# CCM_0008.net
KiCad netlist of a schematic drawn in EAGLE
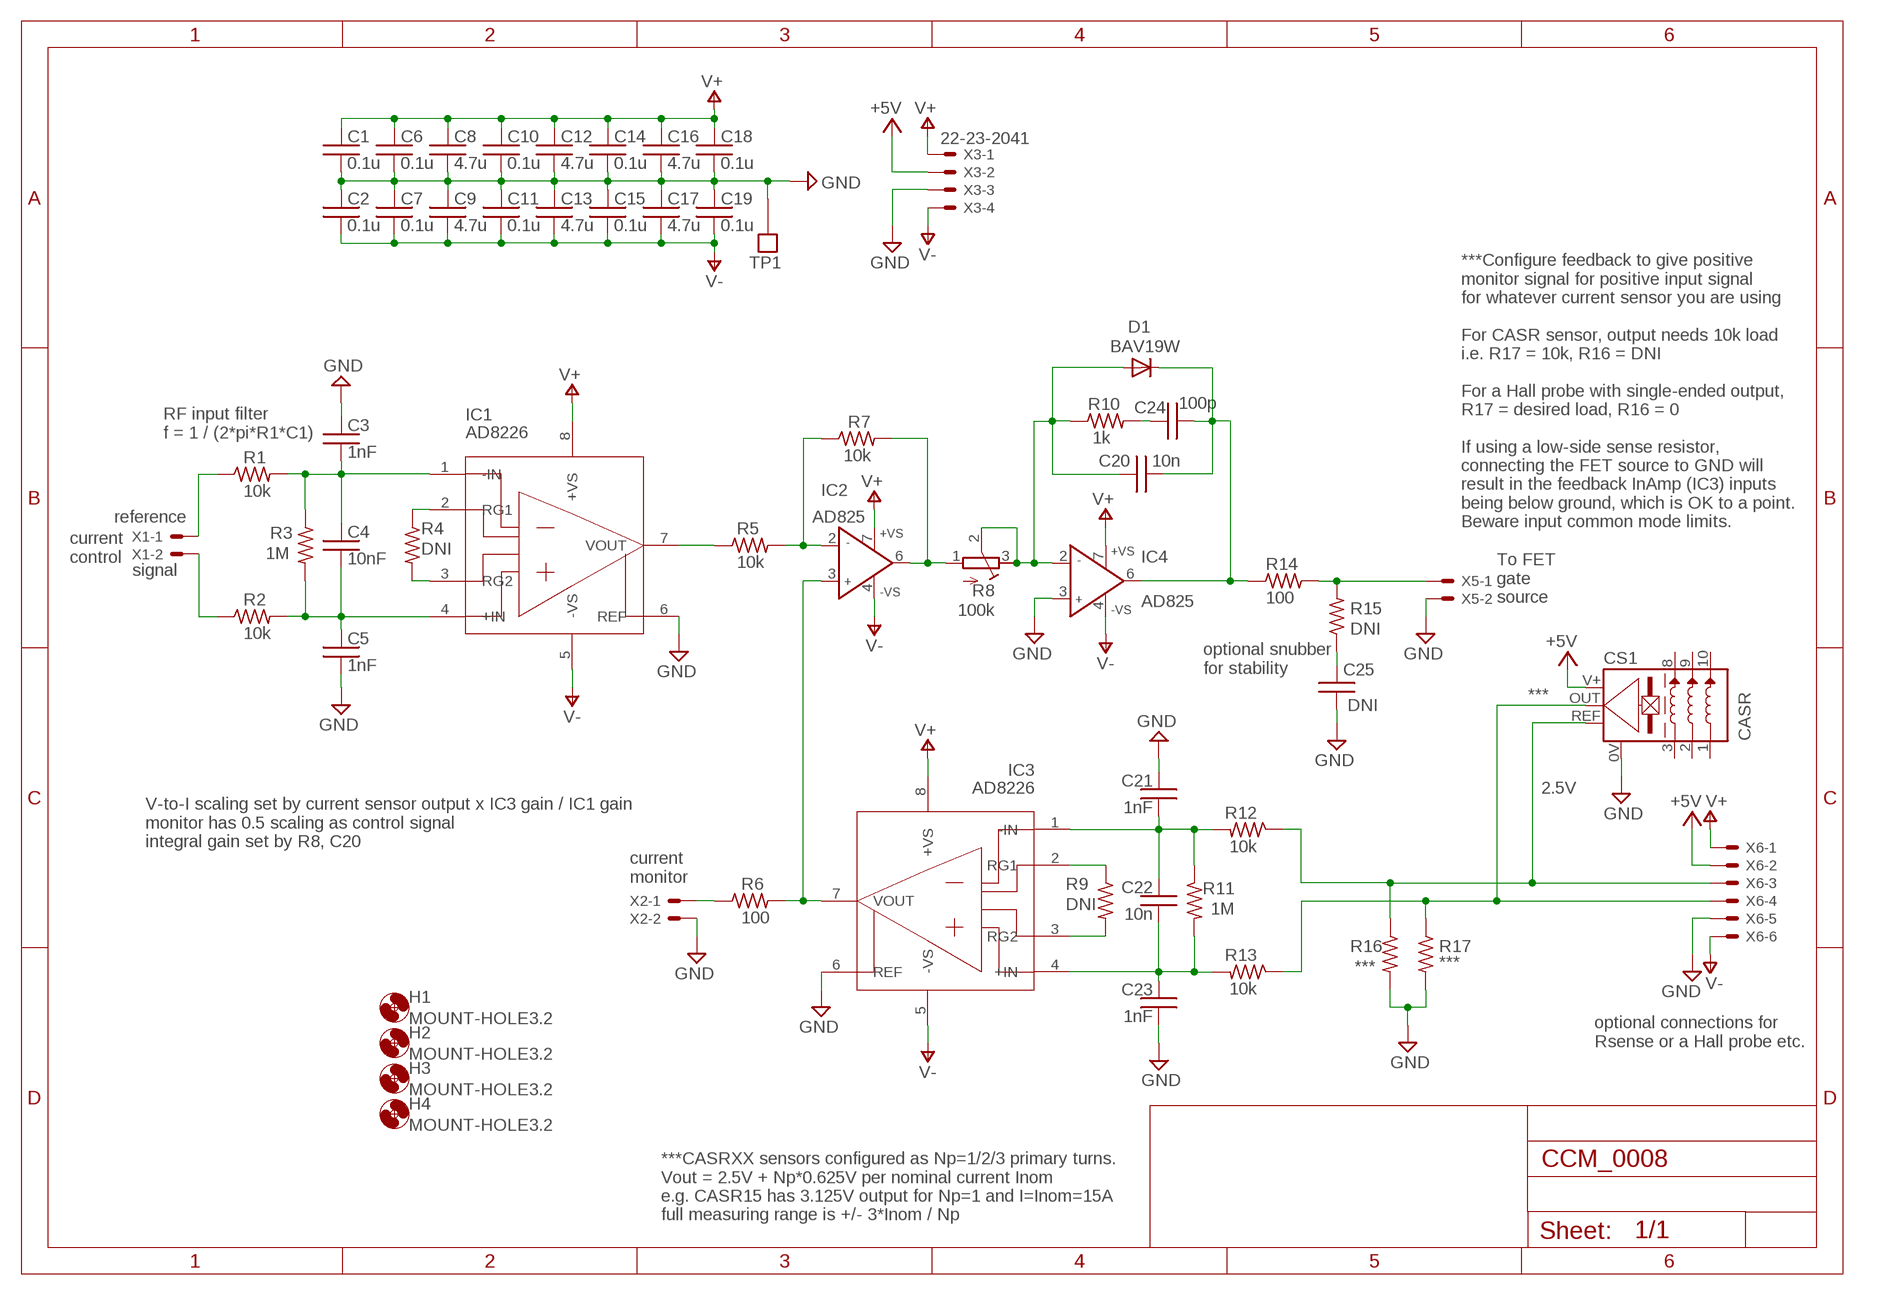
[diagram p0: schematic, sheet 1]

(export (version "E")
  (design (tool "Eeschema 10.0.6"))
  (components
    (comp (ref "C1")
      (value "0.1u")
      (footprint "eagle-import:0603")
      (libsource (lib "eagle-import") (part "C0603"))
    )
    (comp (ref "C2")
      (value "0.1u")
      (footprint "eagle-import:0603")
      (libsource (lib "eagle-import") (part "C0603"))
    )
    (comp (ref "C3")
      (value "1nF")
      (footprint "eagle-import:0603")
      (libsource (lib "eagle-import") (part "C0603"))
    )
    (comp (ref "C4")
      (value "10nF")
      (footprint "eagle-import:0603")
      (libsource (lib "eagle-import") (part "C0603"))
    )
    (comp (ref "C5")
      (value "1nF")
      (footprint "eagle-import:0603")
      (libsource (lib "eagle-import") (part "C0603"))
    )
    (comp (ref "C6")
      (value "0.1u")
      (footprint "eagle-import:0603")
      (libsource (lib "eagle-import") (part "C0603"))
    )
    (comp (ref "C7")
      (value "0.1u")
      (footprint "eagle-import:0603")
      (libsource (lib "eagle-import") (part "C0603"))
    )
    (comp (ref "C8")
      (value "4.7u")
      (footprint "eagle-import:0603")
      (libsource (lib "eagle-import") (part "C0603"))
    )
    (comp (ref "C9")
      (value "4.7u")
      (footprint "eagle-import:0603")
      (libsource (lib "eagle-import") (part "C0603"))
    )
    (comp (ref "C10")
      (value "0.1u")
      (footprint "eagle-import:0603")
      (libsource (lib "eagle-import") (part "C0603"))
    )
    (comp (ref "C11")
      (value "0.1u")
      (footprint "eagle-import:0603")
      (libsource (lib "eagle-import") (part "C0603"))
    )
    (comp (ref "C12")
      (value "4.7u")
      (footprint "eagle-import:0603")
      (libsource (lib "eagle-import") (part "C0603"))
    )
    (comp (ref "C13")
      (value "4.7u")
      (footprint "eagle-import:0603")
      (libsource (lib "eagle-import") (part "C0603"))
    )
    (comp (ref "C14")
      (value "0.1u")
      (footprint "eagle-import:0603")
      (libsource (lib "eagle-import") (part "C0603"))
    )
    (comp (ref "C15")
      (value "0.1u")
      (footprint "eagle-import:0603")
      (libsource (lib "eagle-import") (part "C0603"))
    )
    (comp (ref "C16")
      (value "4.7u")
      (footprint "eagle-import:0603")
      (libsource (lib "eagle-import") (part "C0603"))
    )
    (comp (ref "C17")
      (value "4.7u")
      (footprint "eagle-import:0603")
      (libsource (lib "eagle-import") (part "C0603"))
    )
    (comp (ref "C18")
      (value "0.1u")
      (footprint "eagle-import:0603")
      (libsource (lib "eagle-import") (part "C0603"))
    )
    (comp (ref "C19")
      (value "0.1u")
      (footprint "eagle-import:0603")
      (libsource (lib "eagle-import") (part "C0603"))
    )
    (comp (ref "C20")
      (value "10n")
      (footprint "eagle-import:0603")
      (libsource (lib "eagle-import") (part "C0603"))
    )
    (comp (ref "C21")
      (value "1nF")
      (footprint "eagle-import:0603")
      (libsource (lib "eagle-import") (part "C0603"))
    )
    (comp (ref "C22")
      (value "10n")
      (footprint "eagle-import:0603")
      (libsource (lib "eagle-import") (part "C0603"))
    )
    (comp (ref "C23")
      (value "1nF")
      (footprint "eagle-import:0603")
      (libsource (lib "eagle-import") (part "C0603"))
    )
    (comp (ref "C24")
      (value "100p")
      (footprint "eagle-import:0603")
      (libsource (lib "eagle-import") (part "C0603"))
    )
    (comp (ref "C25")
      (value "DNI")
      (footprint "eagle-import:0603")
      (libsource (lib "eagle-import") (part "C0603"))
    )
    (comp (ref "CS1")
      (value "CASR")
      (footprint "eagle-import:CASR")
      (libsource (lib "eagle-import") (part "CASR"))
    )
    (comp (ref "D1")
      (value "BAV19W")
      (footprint "eagle-import:SOD123")
      (libsource (lib "eagle-import") (part "DIODE-SOD123"))
    )
    (comp (ref "H1")
      (value "MOUNT-HOLE3.2")
      (footprint "eagle-import:3,2")
      (libsource (lib "eagle-import") (part "MOUNT-HOLE3.2"))
    )
    (comp (ref "H2")
      (value "MOUNT-HOLE3.2")
      (footprint "eagle-import:3,2")
      (libsource (lib "eagle-import") (part "MOUNT-HOLE3.2"))
    )
    (comp (ref "H3")
      (value "MOUNT-HOLE3.2")
      (footprint "eagle-import:3,2")
      (libsource (lib "eagle-import") (part "MOUNT-HOLE3.2"))
    )
    (comp (ref "H4")
      (value "MOUNT-HOLE3.2")
      (footprint "eagle-import:3,2")
      (libsource (lib "eagle-import") (part "MOUNT-HOLE3.2"))
    )
    (comp (ref "IC1")
      (value "AD8226")
      (footprint "eagle-import:SO08")
      (libsource (lib "eagle-import") (part "AD8226"))
    )
    (comp (ref "IC2")
      (value "AD825")
      (footprint "eagle-import:SO8")
      (fields (field (name "MF") "ALTERA CORPORATION") (field (name "MPN") "AD825ARZ"))
      (libsource (lib "eagle-import") (part "AD825_BR"))
    )
    (comp (ref "IC3")
      (value "AD8226")
      (footprint "eagle-import:SO08")
      (libsource (lib "eagle-import") (part "AD8226"))
    )
    (comp (ref "IC4")
      (value "AD825")
      (footprint "eagle-import:SO8")
      (fields (field (name "MF") "ALTERA CORPORATION") (field (name "MPN") "AD825ARZ"))
      (libsource (lib "eagle-import") (part "AD825_BR"))
    )
    (comp (ref "R1")
      (value "10k")
      (footprint "eagle-import:0603")
      (libsource (lib "eagle-import") (part "R0603"))
    )
    (comp (ref "R2")
      (value "10k")
      (footprint "eagle-import:0603")
      (libsource (lib "eagle-import") (part "R0603"))
    )
    (comp (ref "R3")
      (value "1M")
      (footprint "eagle-import:0603")
      (libsource (lib "eagle-import") (part "R0603"))
    )
    (comp (ref "R4")
      (value "DNI")
      (footprint "eagle-import:0603")
      (libsource (lib "eagle-import") (part "R0603"))
    )
    (comp (ref "R5")
      (value "10k")
      (footprint "eagle-import:0603")
      (libsource (lib "eagle-import") (part "R0603"))
    )
    (comp (ref "R6")
      (value "100")
      (footprint "eagle-import:0603")
      (libsource (lib "eagle-import") (part "R0603"))
    )
    (comp (ref "R7")
      (value "10k")
      (footprint "eagle-import:0603")
      (libsource (lib "eagle-import") (part "R0603"))
    )
    (comp (ref "R8")
      (value "100k")
      (footprint "eagle-import:RTRIM3296W")
      (libsource (lib "eagle-import") (part "R-TRIMM3296W"))
    )
    (comp (ref "R9")
      (value "DNI")
      (footprint "eagle-import:0603")
      (libsource (lib "eagle-import") (part "R0603"))
    )
    (comp (ref "R10")
      (value "1k")
      (footprint "eagle-import:0603")
      (libsource (lib "eagle-import") (part "R0603"))
    )
    (comp (ref "R11")
      (value "1M")
      (footprint "eagle-import:0603")
      (libsource (lib "eagle-import") (part "R0603"))
    )
    (comp (ref "R12")
      (value "10k")
      (footprint "eagle-import:0603")
      (libsource (lib "eagle-import") (part "R0603"))
    )
    (comp (ref "R13")
      (value "10k")
      (footprint "eagle-import:0603")
      (libsource (lib "eagle-import") (part "R0603"))
    )
    (comp (ref "R14")
      (value "100")
      (footprint "eagle-import:0603")
      (libsource (lib "eagle-import") (part "R0603"))
    )
    (comp (ref "R15")
      (value "DNI")
      (footprint "eagle-import:0603")
      (libsource (lib "eagle-import") (part "R0603"))
    )
    (comp (ref "R16")
      (value "***")
      (footprint "eagle-import:0603")
      (libsource (lib "eagle-import") (part "R0603"))
    )
    (comp (ref "R17")
      (value "***")
      (footprint "eagle-import:0603")
      (libsource (lib "eagle-import") (part "R0603"))
    )
    (comp (ref "TP1")
      (value "TESTPOINT")
      (footprint "eagle-import:TESTPOINT")
      (libsource (lib "eagle-import") (part "TESTPOINT"))
    )
    (comp (ref "X1")
      (value "22-23-2021")
      (footprint "eagle-import:22-23-2021")
      (fields (field (name "MF") "MOLEX"))
      (libsource (lib "eagle-import") (part "22-23-2021"))
    )
    (comp (ref "X2")
      (value "22-23-2021")
      (footprint "eagle-import:22-23-2021")
      (fields (field (name "MF") "MOLEX"))
      (libsource (lib "eagle-import") (part "22-23-2021"))
    )
    (comp (ref "X3")
      (value "22-23-2041")
      (footprint "eagle-import:22-23-2041")
      (fields (field (name "MF") "MOLEX"))
      (libsource (lib "eagle-import") (part "22-23-2041"))
    )
    (comp (ref "X5")
      (value "22-23-2021")
      (footprint "eagle-import:22-23-2021")
      (fields (field (name "MF") "MOLEX"))
      (libsource (lib "eagle-import") (part "22-23-2021"))
    )
    (comp (ref "X6")
      (value "22-23-2061")
      (footprint "eagle-import:22-23-2061")
      (fields (field (name "MF") "MOLEX"))
      (libsource (lib "eagle-import") (part "22-23-2061"))
    )
  )
  (nets
    (net (code "1") (name "+5V") (class "Default")
      (node (ref "CS1") (pin "V+") (pinfunction "V+_V+") (pintype "input"))
      (node (ref "X3") (pin "2") (pinfunction "S_2") (pintype "passive"))
      (node (ref "X6") (pin "2") (pinfunction "S_2") (pintype "passive"))
    )
    (net (code "2") (name "GND") (class "Default")
      (node (ref "C1") (pin "2") (pinfunction "2_2") (pintype "passive"))
      (node (ref "C10") (pin "2") (pinfunction "2_2") (pintype "passive"))
      (node (ref "C11") (pin "1") (pinfunction "1_1") (pintype "passive"))
      (node (ref "C12") (pin "2") (pinfunction "2_2") (pintype "passive"))
      (node (ref "C13") (pin "1") (pinfunction "1_1") (pintype "passive"))
      (node (ref "C14") (pin "2") (pinfunction "2_2") (pintype "passive"))
      (node (ref "C15") (pin "1") (pinfunction "1_1") (pintype "passive"))
      (node (ref "C16") (pin "2") (pinfunction "2_2") (pintype "passive"))
      (node (ref "C17") (pin "1") (pinfunction "1_1") (pintype "passive"))
      (node (ref "C18") (pin "2") (pinfunction "2_2") (pintype "passive"))
      (node (ref "C19") (pin "1") (pinfunction "1_1") (pintype "passive"))
      (node (ref "C2") (pin "1") (pinfunction "1_1") (pintype "passive"))
      (node (ref "C21") (pin "1") (pinfunction "1_1") (pintype "passive"))
      (node (ref "C23") (pin "2") (pinfunction "2_2") (pintype "passive"))
      (node (ref "C25") (pin "2") (pinfunction "2_2") (pintype "passive"))
      (node (ref "C3") (pin "1") (pinfunction "1_1") (pintype "passive"))
      (node (ref "C5") (pin "2") (pinfunction "2_2") (pintype "passive"))
      (node (ref "C6") (pin "2") (pinfunction "2_2") (pintype "passive"))
      (node (ref "C7") (pin "1") (pinfunction "1_1") (pintype "passive"))
      (node (ref "C8") (pin "2") (pinfunction "2_2") (pintype "passive"))
      (node (ref "C9") (pin "1") (pinfunction "1_1") (pintype "passive"))
      (node (ref "CS1") (pin "0V") (pinfunction "0V_0V") (pintype "input"))
      (node (ref "IC1") (pin "6") (pinfunction "REF_6") (pintype "bidirectional"))
      (node (ref "IC3") (pin "6") (pinfunction "REF_6") (pintype "bidirectional"))
      (node (ref "IC4") (pin "3") (pinfunction "IN+_3") (pintype "input"))
      (node (ref "R16") (pin "2") (pinfunction "2_2") (pintype "passive"))
      (node (ref "R17") (pin "2") (pinfunction "2_2") (pintype "passive"))
      (node (ref "TP1") (pin "P$1") (pinfunction "P$1_P$1") (pintype "bidirectional"))
      (node (ref "X2") (pin "2") (pinfunction "S_2") (pintype "passive"))
      (node (ref "X3") (pin "3") (pinfunction "S_3") (pintype "passive"))
      (node (ref "X5") (pin "2") (pinfunction "S_2") (pintype "passive"))
      (node (ref "X6") (pin "5") (pinfunction "S_5") (pintype "passive"))
    )
    (net (code "3") (name "Net-(C24-Pad2)") (class "Default")
      (node (ref "C24") (pin "2") (pinfunction "2_2") (pintype "passive"))
      (node (ref "R10") (pin "2") (pinfunction "2_2") (pintype "passive"))
    )
    (net (code "4") (name "Net-(C25-Pad1)") (class "Default")
      (node (ref "C25") (pin "1") (pinfunction "1_1") (pintype "passive"))
      (node (ref "R15") (pin "1") (pinfunction "1_1") (pintype "passive"))
    )
    (net (code "5") (name "Net-(CS1-VOUT)") (class "Default")
      (node (ref "CS1") (pin "OUT") (pinfunction "VOUT_OUT") (pintype "output"))
      (node (ref "R13") (pin "1") (pinfunction "1_1") (pintype "passive"))
      (node (ref "R17") (pin "1") (pinfunction "1_1") (pintype "passive"))
      (node (ref "X6") (pin "4") (pinfunction "S_4") (pintype "passive"))
    )
    (net (code "6") (name "Net-(CS1-VREF)") (class "Default")
      (node (ref "CS1") (pin "REF") (pinfunction "VREF_REF") (pintype "output"))
      (node (ref "R12") (pin "1") (pinfunction "1_1") (pintype "passive"))
      (node (ref "R16") (pin "1") (pinfunction "1_1") (pintype "passive"))
      (node (ref "X6") (pin "3") (pinfunction "S_3") (pintype "passive"))
    )
    (net (code "7") (name "Net-(IC1-+IN)") (class "Default")
      (node (ref "C4") (pin "2") (pinfunction "2_2") (pintype "passive"))
      (node (ref "C5") (pin "1") (pinfunction "1_1") (pintype "passive"))
      (node (ref "IC1") (pin "4") (pinfunction "+IN_4") (pintype "bidirectional"))
      (node (ref "R2") (pin "2") (pinfunction "2_2") (pintype "passive"))
      (node (ref "R3") (pin "2") (pinfunction "2_2") (pintype "passive"))
    )
    (net (code "8") (name "Net-(IC1--IN)") (class "Default")
      (node (ref "C3") (pin "2") (pinfunction "2_2") (pintype "passive"))
      (node (ref "C4") (pin "1") (pinfunction "1_1") (pintype "passive"))
      (node (ref "IC1") (pin "1") (pinfunction "-IN_1") (pintype "bidirectional"))
      (node (ref "R1") (pin "2") (pinfunction "2_2") (pintype "passive"))
      (node (ref "R3") (pin "1") (pinfunction "1_1") (pintype "passive"))
    )
    (net (code "9") (name "Net-(IC1-RG1)") (class "Default")
      (node (ref "IC1") (pin "2") (pinfunction "RG1_2") (pintype "bidirectional"))
      (node (ref "R4") (pin "1") (pinfunction "1_1") (pintype "passive"))
    )
    (net (code "10") (name "Net-(IC1-RG2)") (class "Default")
      (node (ref "IC1") (pin "3") (pinfunction "RG2_3") (pintype "bidirectional"))
      (node (ref "R4") (pin "2") (pinfunction "2_2") (pintype "passive"))
    )
    (net (code "11") (name "Net-(IC1-VOUT)") (class "Default")
      (node (ref "IC1") (pin "7") (pinfunction "VOUT_7") (pintype "bidirectional"))
      (node (ref "R5") (pin "1") (pinfunction "1_1") (pintype "passive"))
    )
    (net (code "12") (name "Net-(IC2-IN+)") (class "Default")
      (node (ref "IC2") (pin "3") (pinfunction "IN+_3") (pintype "input"))
      (node (ref "IC3") (pin "7") (pinfunction "VOUT_7") (pintype "bidirectional"))
      (node (ref "R6") (pin "2") (pinfunction "2_2") (pintype "passive"))
    )
    (net (code "13") (name "Net-(IC2-IN-)") (class "Default")
      (node (ref "IC2") (pin "2") (pinfunction "IN-_2") (pintype "input"))
      (node (ref "R5") (pin "2") (pinfunction "2_2") (pintype "passive"))
      (node (ref "R7") (pin "1") (pinfunction "1_1") (pintype "passive"))
    )
    (net (code "14") (name "Net-(IC2-OUT)") (class "Default")
      (node (ref "IC2") (pin "6") (pinfunction "OUT_6") (pintype "output"))
      (node (ref "R7") (pin "2") (pinfunction "2_2") (pintype "passive"))
      (node (ref "R8") (pin "1") (pinfunction "A_1") (pintype "passive"))
    )
    (net (code "15") (name "Net-(IC3-+IN)") (class "Default")
      (node (ref "C22") (pin "2") (pinfunction "2_2") (pintype "passive"))
      (node (ref "C23") (pin "1") (pinfunction "1_1") (pintype "passive"))
      (node (ref "IC3") (pin "4") (pinfunction "+IN_4") (pintype "bidirectional"))
      (node (ref "R11") (pin "2") (pinfunction "2_2") (pintype "passive"))
      (node (ref "R13") (pin "2") (pinfunction "2_2") (pintype "passive"))
    )
    (net (code "16") (name "Net-(IC3--IN)") (class "Default")
      (node (ref "C21") (pin "2") (pinfunction "2_2") (pintype "passive"))
      (node (ref "C22") (pin "1") (pinfunction "1_1") (pintype "passive"))
      (node (ref "IC3") (pin "1") (pinfunction "-IN_1") (pintype "bidirectional"))
      (node (ref "R11") (pin "1") (pinfunction "1_1") (pintype "passive"))
      (node (ref "R12") (pin "2") (pinfunction "2_2") (pintype "passive"))
    )
    (net (code "17") (name "Net-(IC3-RG1)") (class "Default")
      (node (ref "IC3") (pin "2") (pinfunction "RG1_2") (pintype "bidirectional"))
      (node (ref "R9") (pin "1") (pinfunction "1_1") (pintype "passive"))
    )
    (net (code "18") (name "Net-(IC3-RG2)") (class "Default")
      (node (ref "IC3") (pin "3") (pinfunction "RG2_3") (pintype "bidirectional"))
      (node (ref "R9") (pin "2") (pinfunction "2_2") (pintype "passive"))
    )
    (net (code "19") (name "Net-(IC4-IN-)") (class "Default")
      (node (ref "C20") (pin "2") (pinfunction "2_2") (pintype "passive"))
      (node (ref "D1") (pin "A") (pinfunction "A_A") (pintype "passive"))
      (node (ref "IC4") (pin "2") (pinfunction "IN-_2") (pintype "input"))
      (node (ref "R10") (pin "1") (pinfunction "1_1") (pintype "passive"))
      (node (ref "R8") (pin "2") (pinfunction "S_2") (pintype "passive"))
      (node (ref "R8") (pin "3") (pinfunction "E_3") (pintype "passive"))
    )
    (net (code "20") (name "Net-(IC4-OUT)") (class "Default")
      (node (ref "C20") (pin "1") (pinfunction "1_1") (pintype "passive"))
      (node (ref "C24") (pin "1") (pinfunction "1_1") (pintype "passive"))
      (node (ref "D1") (pin "C") (pinfunction "C_C") (pintype "passive"))
      (node (ref "IC4") (pin "6") (pinfunction "OUT_6") (pintype "output"))
      (node (ref "R14") (pin "1") (pinfunction "1_1") (pintype "passive"))
    )
    (net (code "21") (name "Net-(X1A-S)") (class "Default")
      (node (ref "R1") (pin "1") (pinfunction "1_1") (pintype "passive"))
      (node (ref "X1") (pin "1") (pinfunction "S_1") (pintype "passive"))
    )
    (net (code "22") (name "Net-(X1B-S)") (class "Default")
      (node (ref "R2") (pin "1") (pinfunction "1_1") (pintype "passive"))
      (node (ref "X1") (pin "2") (pinfunction "S_2") (pintype "passive"))
    )
    (net (code "23") (name "Net-(X2A-S)") (class "Default")
      (node (ref "R6") (pin "1") (pinfunction "1_1") (pintype "passive"))
      (node (ref "X2") (pin "1") (pinfunction "S_1") (pintype "passive"))
    )
    (net (code "24") (name "Net-(X5A-S)") (class "Default")
      (node (ref "R14") (pin "2") (pinfunction "2_2") (pintype "passive"))
      (node (ref "R15") (pin "2") (pinfunction "2_2") (pintype "passive"))
      (node (ref "X5") (pin "1") (pinfunction "S_1") (pintype "passive"))
    )
    (net (code "25") (name "V+") (class "Default")
      (node (ref "C1") (pin "1") (pinfunction "1_1") (pintype "passive"))
      (node (ref "C10") (pin "1") (pinfunction "1_1") (pintype "passive"))
      (node (ref "C12") (pin "1") (pinfunction "1_1") (pintype "passive"))
      (node (ref "C14") (pin "1") (pinfunction "1_1") (pintype "passive"))
      (node (ref "C16") (pin "1") (pinfunction "1_1") (pintype "passive"))
      (node (ref "C18") (pin "1") (pinfunction "1_1") (pintype "passive"))
      (node (ref "C6") (pin "1") (pinfunction "1_1") (pintype "passive"))
      (node (ref "C8") (pin "1") (pinfunction "1_1") (pintype "passive"))
      (node (ref "IC1") (pin "8") (pinfunction "+VS_8") (pintype "bidirectional"))
      (node (ref "IC2") (pin "7") (pinfunction "+VS_7") (pintype "input"))
      (node (ref "IC3") (pin "8") (pinfunction "+VS_8") (pintype "bidirectional"))
      (node (ref "IC4") (pin "7") (pinfunction "+VS_7") (pintype "input"))
      (node (ref "X3") (pin "1") (pinfunction "S_1") (pintype "passive"))
      (node (ref "X6") (pin "1") (pinfunction "S_1") (pintype "passive"))
    )
    (net (code "26") (name "V-") (class "Default")
      (node (ref "C11") (pin "2") (pinfunction "2_2") (pintype "passive"))
      (node (ref "C13") (pin "2") (pinfunction "2_2") (pintype "passive"))
      (node (ref "C15") (pin "2") (pinfunction "2_2") (pintype "passive"))
      (node (ref "C17") (pin "2") (pinfunction "2_2") (pintype "passive"))
      (node (ref "C19") (pin "2") (pinfunction "2_2") (pintype "passive"))
      (node (ref "C2") (pin "2") (pinfunction "2_2") (pintype "passive"))
      (node (ref "C7") (pin "2") (pinfunction "2_2") (pintype "passive"))
      (node (ref "C9") (pin "2") (pinfunction "2_2") (pintype "passive"))
      (node (ref "IC1") (pin "5") (pinfunction "-VS_5") (pintype "bidirectional"))
      (node (ref "IC2") (pin "4") (pinfunction "-VS_4") (pintype "input"))
      (node (ref "IC3") (pin "5") (pinfunction "-VS_5") (pintype "bidirectional"))
      (node (ref "IC4") (pin "4") (pinfunction "-VS_4") (pintype "input"))
      (node (ref "X3") (pin "4") (pinfunction "S_4") (pintype "passive"))
      (node (ref "X6") (pin "6") (pinfunction "S_6") (pintype "passive"))
    )
    (net (code "27") (name "unconnected-(CS1-IN1-Pad1)") (class "Default")
      (node (ref "CS1") (pin "1") (pinfunction "IN1_1") (pintype "input"))
    )
    (net (code "28") (name "unconnected-(CS1-IN2-Pad2)") (class "Default")
      (node (ref "CS1") (pin "2") (pinfunction "IN2_2") (pintype "input"))
    )
    (net (code "29") (name "unconnected-(CS1-IN3-Pad3)") (class "Default")
      (node (ref "CS1") (pin "3") (pinfunction "IN3_3") (pintype "input"))
    )
    (net (code "30") (name "unconnected-(CS1-OUT8-Pad8)") (class "Default")
      (node (ref "CS1") (pin "8") (pinfunction "OUT8_8") (pintype "input"))
    )
    (net (code "31") (name "unconnected-(CS1-OUT9-Pad9)") (class "Default")
      (node (ref "CS1") (pin "9") (pinfunction "OUT9_9") (pintype "input"))
    )
    (net (code "32") (name "unconnected-(CS1-OUT10-Pad10)") (class "Default")
      (node (ref "CS1") (pin "10") (pinfunction "OUT10_10") (pintype "input"))
    )
  )
)
